# Main.net
KiCad netlist of a schematic drawn in Altium Designer
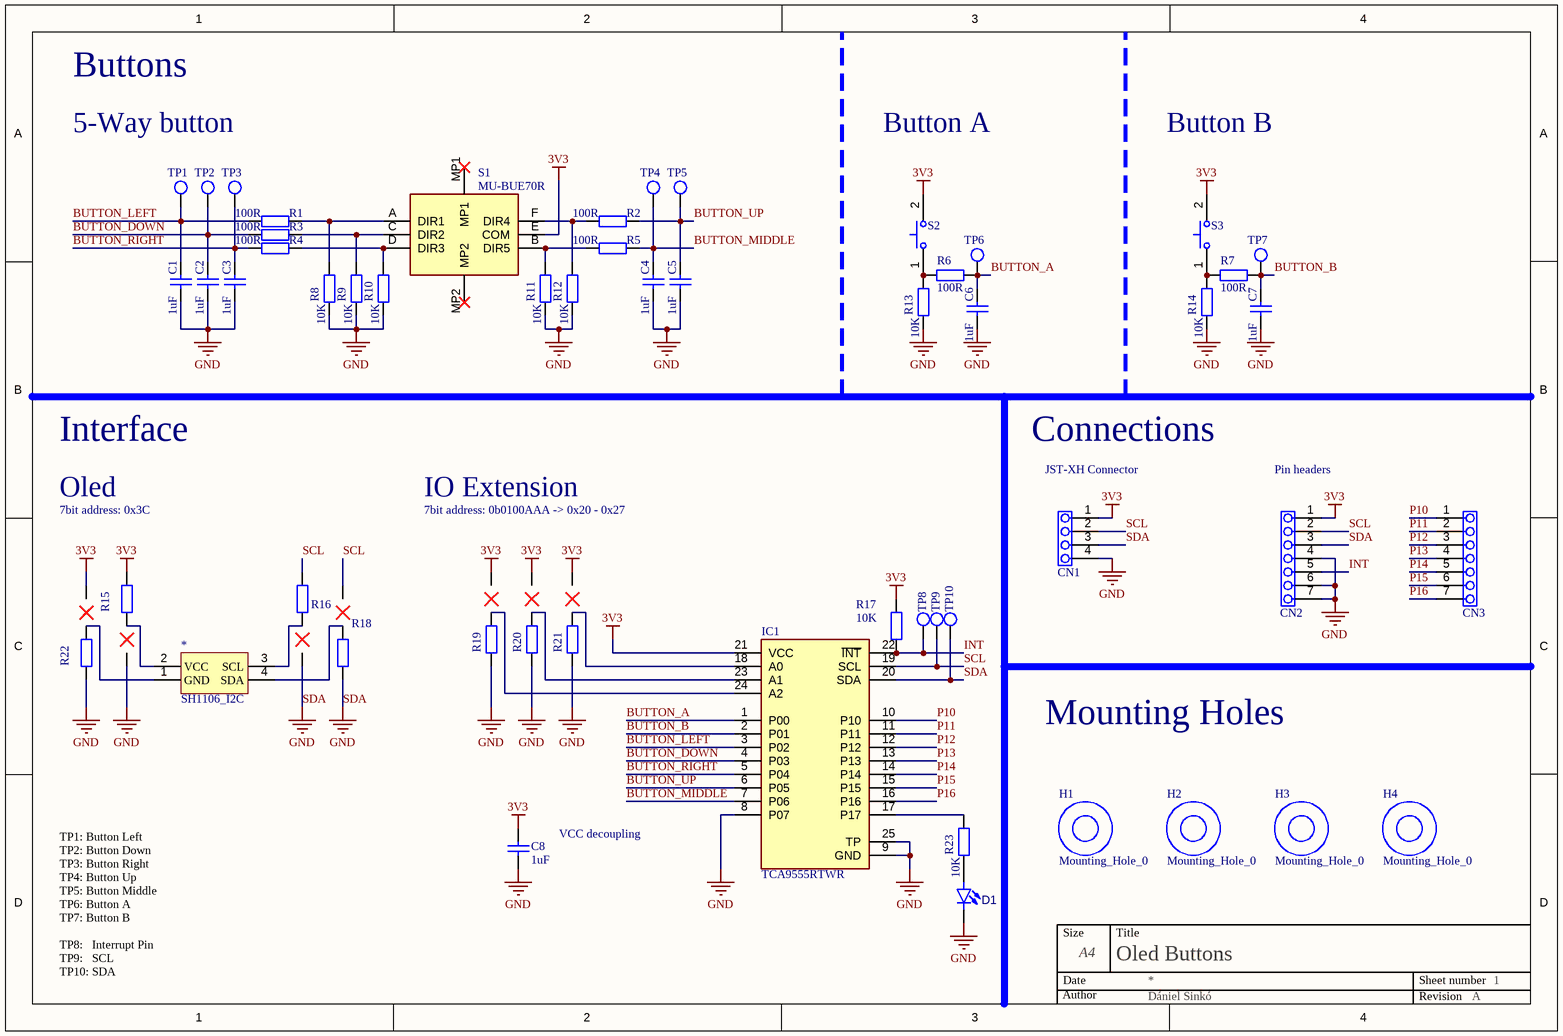
[diagram p0: Main.SchDoc]

(export (version "E")
  (design (tool "Eeschema 10.0.6"))
  (components
    (comp (ref "*")
      (value "SH1106_I2C")
      (footprint "SH1106_I2C")
      (libsource (lib "Generic_Schematic_Symbols") (part "SH1106_I2C"))
    )
    (comp (ref "C1")
      (value "1uF")
      (footprint "CAP0603")
      (description "Capacitor")
      (libsource (lib "Generic_Schematic_Symbols") (part "Capacitor"))
    )
    (comp (ref "C2")
      (value "1uF")
      (footprint "CAP0603")
      (description "Capacitor")
      (libsource (lib "Generic_Schematic_Symbols") (part "Capacitor"))
    )
    (comp (ref "C3")
      (value "1uF")
      (footprint "CAP0603")
      (description "Capacitor")
      (libsource (lib "Generic_Schematic_Symbols") (part "Capacitor"))
    )
    (comp (ref "C4")
      (value "1uF")
      (footprint "CAP0603")
      (description "Capacitor")
      (libsource (lib "Generic_Schematic_Symbols") (part "Capacitor"))
    )
    (comp (ref "C5")
      (value "1uF")
      (footprint "CAP0603")
      (description "Capacitor")
      (libsource (lib "Generic_Schematic_Symbols") (part "Capacitor"))
    )
    (comp (ref "C6")
      (value "1uF")
      (footprint "CAP0603")
      (description "Capacitor")
      (libsource (lib "Generic_Schematic_Symbols") (part "Capacitor"))
    )
    (comp (ref "C7")
      (value "1uF")
      (footprint "CAP0603")
      (description "Capacitor")
      (libsource (lib "Generic_Schematic_Symbols") (part "Capacitor"))
    )
    (comp (ref "C8")
      (value "1uF")
      (footprint "CAP0603")
      (description "Capacitor")
      (libsource (lib "Generic_Schematic_Symbols") (part "Capacitor"))
    )
    (comp (ref "CN1")
      (value "Pins 1x3")
      (footprint "PIN-1X4")
      (description "2.54mm")
      (libsource (lib "Generic_Schematic_Symbols") (part "Pin-1x4"))
    )
    (comp (ref "CN2")
      (value "Pins 1x3")
      (footprint "PIN-1X7")
      (description "2.54mm")
      (libsource (lib "Generic_Schematic_Symbols") (part "Pin-1x7"))
    )
    (comp (ref "CN3")
      (value "Pins 1x3")
      (footprint "PIN-1X7")
      (description "2.54mm")
      (libsource (lib "Generic_Schematic_Symbols") (part "Pin-1x7"))
    )
    (comp (ref "D1")
      (value "~")
      (footprint "LED0603")
      (description "Light Emitting Diode")
      (libsource (lib "Generic_Schematic_Symbols") (part "LED"))
    )
    (comp (ref "H1")
      (value "Mounting_Hole_0")
      (footprint "MOUNTING_HOLE_M3_0")
      (description "Mounting hole with no connectivity.")
      (libsource (lib "Generic_Schematic_Symbols") (part "Mounting_Hole_0"))
    )
    (comp (ref "H2")
      (value "Mounting_Hole_0")
      (footprint "MOUNTING_HOLE_M3_0")
      (description "Mounting hole with no connectivity.")
      (libsource (lib "Generic_Schematic_Symbols") (part "Mounting_Hole_0"))
    )
    (comp (ref "H3")
      (value "Mounting_Hole_0")
      (footprint "MOUNTING_HOLE_M3_0")
      (description "Mounting hole with no connectivity.")
      (libsource (lib "Generic_Schematic_Symbols") (part "Mounting_Hole_0"))
    )
    (comp (ref "H4")
      (value "Mounting_Hole_0")
      (footprint "MOUNTING_HOLE_M3_0")
      (description "Mounting hole with no connectivity.")
      (libsource (lib "Generic_Schematic_Symbols") (part "Mounting_Hole_0"))
    )
    (comp (ref "IC1")
      (value "TCA9555RTWR")
      (footprint "WQFN-24")
      (description "Integrated Circuit")
      (fields
        (field (name "MOUSER PART NUMBER") "595-TCA9555RTWR")
        (field (name "LCSC PART NUMBER") "C42420609")
      )
      (libsource (lib "Generic_Schematic_Symbols") (part "TCA9555RTWR"))
    )
    (comp (ref "R1")
      (value "100R")
      (footprint "RES0603")
      (description "Resistor")
      (libsource (lib "") (part "Resistor_1"))
    )
    (comp (ref "R2")
      (value "100R")
      (footprint "RES0603")
      (description "Resistor")
      (libsource (lib "") (part "Resistor_1"))
    )
    (comp (ref "R3")
      (value "100R")
      (footprint "RES0603")
      (description "Resistor")
      (libsource (lib "") (part "Resistor_1"))
    )
    (comp (ref "R4")
      (value "100R")
      (footprint "RES0603")
      (description "Resistor")
      (libsource (lib "") (part "Resistor_1"))
    )
    (comp (ref "R5")
      (value "100R")
      (footprint "RES0603")
      (description "Resistor")
      (libsource (lib "") (part "Resistor_1"))
    )
    (comp (ref "R6")
      (value "100R")
      (footprint "RES0603")
      (description "Resistor")
      (libsource (lib "") (part "Resistor_1"))
    )
    (comp (ref "R7")
      (value "100R")
      (footprint "RES0603")
      (description "Resistor")
      (libsource (lib "") (part "Resistor_1"))
    )
    (comp (ref "R8")
      (value "10K")
      (footprint "RES0603")
      (description "Resistor")
      (libsource (lib "Generic_Schematic_Symbols") (part "Resistor"))
    )
    (comp (ref "R9")
      (value "10K")
      (footprint "RES0603")
      (description "Resistor")
      (libsource (lib "Generic_Schematic_Symbols") (part "Resistor"))
    )
    (comp (ref "R10")
      (value "10K")
      (footprint "RES0603")
      (description "Resistor")
      (libsource (lib "Generic_Schematic_Symbols") (part "Resistor"))
    )
    (comp (ref "R11")
      (value "10K")
      (footprint "RES0603")
      (description "Resistor")
      (libsource (lib "Generic_Schematic_Symbols") (part "Resistor"))
    )
    (comp (ref "R12")
      (value "10K")
      (footprint "RES0603")
      (description "Resistor")
      (libsource (lib "Generic_Schematic_Symbols") (part "Resistor"))
    )
    (comp (ref "R13")
      (value "10K")
      (footprint "RES0603")
      (description "Resistor")
      (libsource (lib "Generic_Schematic_Symbols") (part "Resistor"))
    )
    (comp (ref "R14")
      (value "10K")
      (footprint "RES0603")
      (description "Resistor")
      (libsource (lib "Generic_Schematic_Symbols") (part "Resistor"))
    )
    (comp (ref "R15")
      (value "*")
      (footprint "RES0603 _SELECTION")
      (description "Resistor")
      (libsource (lib "") (part "Resistor_Selection_1"))
    )
    (comp (ref "R16")
      (value "*")
      (footprint "RES0603 _SELECTION")
      (description "Resistor")
      (libsource (lib "") (part "Resistor_Selection_2"))
    )
    (comp (ref "R17")
      (value "10K")
      (footprint "RES0603")
      (description "Resistor")
      (libsource (lib "Generic_Schematic_Symbols") (part "Resistor"))
    )
    (comp (ref "R18")
      (value "*")
      (footprint "RES0603 _SELECTION")
      (description "Resistor")
      (libsource (lib "Generic_Schematic_Symbols") (part "Resistor_Selection"))
    )
    (comp (ref "R19")
      (value "*")
      (footprint "RES0603 _SELECTION")
      (description "Resistor")
      (libsource (lib "Generic_Schematic_Symbols") (part "Resistor_Selection"))
    )
    (comp (ref "R20")
      (value "*")
      (footprint "RES0603 _SELECTION")
      (description "Resistor")
      (libsource (lib "Generic_Schematic_Symbols") (part "Resistor_Selection"))
    )
    (comp (ref "R21")
      (value "*")
      (footprint "RES0603 _SELECTION")
      (description "Resistor")
      (libsource (lib "Generic_Schematic_Symbols") (part "Resistor_Selection"))
    )
    (comp (ref "R22")
      (value "*")
      (footprint "RES0603 _SELECTION")
      (description "Resistor")
      (libsource (lib "") (part "Resistor_Selection_3"))
    )
    (comp (ref "R23")
      (value "10K")
      (footprint "RES0603")
      (description "Resistor")
      (libsource (lib "Generic_Schematic_Symbols") (part "Resistor"))
    )
    (comp (ref "S1")
      (value "MU-BUE70R")
      (footprint "MUBUE70R")
      (description "Switch")
      (fields (field (name "LCSC PART NUMBER") "C2858287"))
      (libsource (lib "Buttons") (part "MU-BUE70R"))
    )
    (comp (ref "S2")
      (value "SKPMANE010")
      (footprint "SKPMAPE010")
      (description "Switch (2-Pin Push)")
      (fields (field (name "MOUSER PART NUMBER") "688-SKPMAN"))
      (libsource (lib "Buttons") (part "SKPMANE010"))
    )
    (comp (ref "S3")
      (value "SKPMANE010")
      (footprint "SKPMAPE010")
      (description "Switch (2-Pin Push)")
      (fields (field (name "MOUSER PART NUMBER") "688-SKPMAN"))
      (libsource (lib "Buttons") (part "SKPMANE010"))
    )
    (comp (ref "TP1")
      (value "Test Point")
      (footprint "TP_PAD")
      (libsource (lib "Generic_Schematic_Symbols") (part "Test Point"))
    )
    (comp (ref "TP2")
      (value "Test Point")
      (footprint "TP_PAD")
      (libsource (lib "Generic_Schematic_Symbols") (part "Test Point"))
    )
    (comp (ref "TP3")
      (value "Test Point")
      (footprint "TP_PAD")
      (libsource (lib "Generic_Schematic_Symbols") (part "Test Point"))
    )
    (comp (ref "TP4")
      (value "Test Point")
      (footprint "TP_PAD")
      (libsource (lib "Generic_Schematic_Symbols") (part "Test Point"))
    )
    (comp (ref "TP5")
      (value "Test Point")
      (footprint "TP_PAD")
      (libsource (lib "Generic_Schematic_Symbols") (part "Test Point"))
    )
    (comp (ref "TP6")
      (value "Test Point")
      (footprint "TP_PAD")
      (libsource (lib "Generic_Schematic_Symbols") (part "Test Point"))
    )
    (comp (ref "TP7")
      (value "Test Point")
      (footprint "TP_PAD")
      (libsource (lib "Generic_Schematic_Symbols") (part "Test Point"))
    )
    (comp (ref "TP8")
      (value "Test Point")
      (footprint "TP_PAD")
      (libsource (lib "Generic_Schematic_Symbols") (part "Test Point"))
    )
    (comp (ref "TP9")
      (value "Test Point")
      (footprint "TP_PAD")
      (libsource (lib "Generic_Schematic_Symbols") (part "Test Point"))
    )
    (comp (ref "TP10")
      (value "Test Point")
      (footprint "TP_PAD")
      (libsource (lib "Generic_Schematic_Symbols") (part "Test Point"))
    )
  )
  (nets
    (net (code "1") (name "/BUTTON_A") (class "Default")
      (node (ref "C6") (pin "2") (pinfunction "2_2") (pintype "passive"))
      (node (ref "IC1") (pin "1") (pinfunction "P00_1") (pintype "passive"))
      (node (ref "R6") (pin "1") (pinfunction "1_1") (pintype "passive"))
      (node (ref "TP6") (pin "1") (pintype "passive"))
    )
    (net (code "2") (name "/BUTTON_B") (class "Default")
      (node (ref "C7") (pin "2") (pinfunction "2_2") (pintype "passive"))
      (node (ref "IC1") (pin "2") (pinfunction "P01_2") (pintype "passive"))
      (node (ref "R7") (pin "1") (pinfunction "1_1") (pintype "passive"))
      (node (ref "TP7") (pin "1") (pintype "passive"))
    )
    (net (code "3") (name "/BUTTON_DOWN") (class "Default")
      (node (ref "C2") (pin "2") (pinfunction "2_2") (pintype "passive"))
      (node (ref "IC1") (pin "4") (pinfunction "P03_4") (pintype "passive"))
      (node (ref "R3") (pin "2") (pinfunction "2_2") (pintype "passive"))
      (node (ref "TP2") (pin "1") (pintype "passive"))
    )
    (net (code "4") (name "/BUTTON_LEFT") (class "Default")
      (node (ref "C1") (pin "2") (pinfunction "2_2") (pintype "passive"))
      (node (ref "IC1") (pin "3") (pinfunction "P02_3") (pintype "passive"))
      (node (ref "R1") (pin "2") (pinfunction "2_2") (pintype "passive"))
      (node (ref "TP1") (pin "1") (pintype "passive"))
    )
    (net (code "5") (name "/BUTTON_MIDDLE") (class "Default")
      (node (ref "C4") (pin "2") (pinfunction "2_2") (pintype "passive"))
      (node (ref "IC1") (pin "7") (pinfunction "P06_7") (pintype "passive"))
      (node (ref "R5") (pin "1") (pinfunction "1_1") (pintype "passive"))
      (node (ref "TP4") (pin "1") (pintype "passive"))
    )
    (net (code "6") (name "/BUTTON_RIGHT") (class "Default")
      (node (ref "C3") (pin "2") (pinfunction "2_2") (pintype "passive"))
      (node (ref "IC1") (pin "5") (pinfunction "P04_5") (pintype "passive"))
      (node (ref "R4") (pin "2") (pinfunction "2_2") (pintype "passive"))
      (node (ref "TP3") (pin "1") (pintype "passive"))
    )
    (net (code "7") (name "/BUTTON_UP") (class "Default")
      (node (ref "C5") (pin "2") (pinfunction "2_2") (pintype "passive"))
      (node (ref "IC1") (pin "6") (pinfunction "P05_6") (pintype "passive"))
      (node (ref "R2") (pin "1") (pinfunction "1_1") (pintype "passive"))
      (node (ref "TP5") (pin "1") (pintype "passive"))
    )
    (net (code "8") (name "/INT") (class "Default")
      (node (ref "CN2") (pin "5") (pinfunction "5_5") (pintype "passive"))
      (node (ref "IC1") (pin "22") (pinfunction "~{INT}_22") (pintype "passive"))
      (node (ref "R17") (pin "1") (pinfunction "1_1") (pintype "passive"))
      (node (ref "TP8") (pin "1") (pintype "passive"))
    )
    (net (code "9") (name "/P10") (class "Default")
      (node (ref "CN3") (pin "1") (pinfunction "1_1") (pintype "passive"))
      (node (ref "IC1") (pin "10") (pinfunction "P10_10") (pintype "passive"))
    )
    (net (code "10") (name "/P11") (class "Default")
      (node (ref "CN3") (pin "2") (pinfunction "2_2") (pintype "passive"))
      (node (ref "IC1") (pin "11") (pinfunction "P11_11") (pintype "passive"))
    )
    (net (code "11") (name "/P12") (class "Default")
      (node (ref "CN3") (pin "3") (pinfunction "3_3") (pintype "passive"))
      (node (ref "IC1") (pin "12") (pinfunction "P12_12") (pintype "passive"))
    )
    (net (code "12") (name "/P13") (class "Default")
      (node (ref "CN3") (pin "4") (pinfunction "4_4") (pintype "passive"))
      (node (ref "IC1") (pin "13") (pinfunction "P13_13") (pintype "passive"))
    )
    (net (code "13") (name "/P14") (class "Default")
      (node (ref "CN3") (pin "5") (pinfunction "5_5") (pintype "passive"))
      (node (ref "IC1") (pin "14") (pinfunction "P14_14") (pintype "passive"))
    )
    (net (code "14") (name "/P15") (class "Default")
      (node (ref "CN3") (pin "6") (pinfunction "6_6") (pintype "passive"))
      (node (ref "IC1") (pin "15") (pinfunction "P15_15") (pintype "passive"))
    )
    (net (code "15") (name "/P16") (class "Default")
      (node (ref "CN3") (pin "7") (pinfunction "7_7") (pintype "passive"))
      (node (ref "IC1") (pin "16") (pinfunction "P16_16") (pintype "passive"))
    )
    (net (code "16") (name "/SCL") (class "Default")
      (node (ref "CN1") (pin "2") (pinfunction "2_2") (pintype "passive"))
      (node (ref "CN2") (pin "2") (pinfunction "2_2") (pintype "passive"))
      (node (ref "IC1") (pin "19") (pinfunction "SCL_19") (pintype "passive"))
      (node (ref "R16") (pin "1") (pinfunction "1_1") (pintype "passive"))
      (node (ref "R18") (pin "3") (pinfunction "3_3") (pintype "passive"))
      (node (ref "TP9") (pin "1") (pintype "passive"))
    )
    (net (code "17") (name "3V3") (class "Default")
      (node (ref "C8") (pin "2") (pinfunction "2_2") (pintype "passive"))
      (node (ref "CN1") (pin "1") (pinfunction "1_1") (pintype "passive"))
      (node (ref "CN2") (pin "1") (pinfunction "1_1") (pintype "passive"))
      (node (ref "IC1") (pin "21") (pinfunction "VCC_21") (pintype "passive"))
      (node (ref "R15") (pin "1") (pinfunction "1_1") (pintype "passive"))
      (node (ref "R17") (pin "2") (pinfunction "2_2") (pintype "passive"))
      (node (ref "R19") (pin "3") (pinfunction "3_3") (pintype "passive"))
      (node (ref "R20") (pin "3") (pinfunction "3_3") (pintype "passive"))
      (node (ref "R21") (pin "3") (pinfunction "3_3") (pintype "passive"))
      (node (ref "R22") (pin "3") (pinfunction "3_3") (pintype "passive"))
      (node (ref "S1") (pin "E") (pinfunction "COM_E") (pintype "passive"))
      (node (ref "S2") (pin "2") (pinfunction "2_2") (pintype "passive"))
      (node (ref "S3") (pin "2") (pinfunction "2_2") (pintype "passive"))
    )
    (net (code "18") (name "GND") (class "Default")
      (node (ref "C1") (pin "1") (pinfunction "1_1") (pintype "passive"))
      (node (ref "C2") (pin "1") (pinfunction "1_1") (pintype "passive"))
      (node (ref "C3") (pin "1") (pinfunction "1_1") (pintype "passive"))
      (node (ref "C4") (pin "1") (pinfunction "1_1") (pintype "passive"))
      (node (ref "C5") (pin "1") (pinfunction "1_1") (pintype "passive"))
      (node (ref "C6") (pin "1") (pinfunction "1_1") (pintype "passive"))
      (node (ref "C7") (pin "1") (pinfunction "1_1") (pintype "passive"))
      (node (ref "C8") (pin "1") (pinfunction "1_1") (pintype "passive"))
      (node (ref "CN1") (pin "3") (pinfunction "3_3") (pintype "passive"))
      (node (ref "CN1") (pin "4") (pinfunction "4_4") (pintype "passive"))
      (node (ref "CN2") (pin "3") (pinfunction "3_3") (pintype "passive"))
      (node (ref "CN2") (pin "4") (pinfunction "4_4") (pintype "passive"))
      (node (ref "CN2") (pin "6") (pinfunction "6_6") (pintype "passive"))
      (node (ref "CN2") (pin "7") (pinfunction "7_7") (pintype "passive"))
      (node (ref "D1") (pin "1") (pinfunction "K_1") (pintype "passive"))
      (node (ref "IC1") (pin "20") (pinfunction "SDA_20") (pintype "passive"))
      (node (ref "IC1") (pin "25") (pinfunction "TP_25") (pintype "passive"))
      (node (ref "IC1") (pin "8") (pinfunction "P07_8") (pintype "passive"))
      (node (ref "IC1") (pin "9") (pinfunction "GND_9") (pintype "passive"))
      (node (ref "R10") (pin "1") (pinfunction "1_1") (pintype "passive"))
      (node (ref "R11") (pin "1") (pinfunction "1_1") (pintype "passive"))
      (node (ref "R12") (pin "1") (pinfunction "1_1") (pintype "passive"))
      (node (ref "R13") (pin "1") (pinfunction "1_1") (pintype "passive"))
      (node (ref "R14") (pin "1") (pinfunction "1_1") (pintype "passive"))
      (node (ref "R15") (pin "3") (pinfunction "3_3") (pintype "passive"))
      (node (ref "R16") (pin "3") (pinfunction "3_3") (pintype "passive"))
      (node (ref "R18") (pin "1") (pinfunction "1_1") (pintype "passive"))
      (node (ref "R19") (pin "1") (pinfunction "1_1") (pintype "passive"))
      (node (ref "R20") (pin "1") (pinfunction "1_1") (pintype "passive"))
      (node (ref "R21") (pin "1") (pinfunction "1_1") (pintype "passive"))
      (node (ref "R22") (pin "1") (pinfunction "1_1") (pintype "passive"))
      (node (ref "R8") (pin "1") (pinfunction "1_1") (pintype "passive"))
      (node (ref "R9") (pin "1") (pinfunction "1_1") (pintype "passive"))
      (node (ref "TP10") (pin "1") (pintype "passive"))
    )
    (net (code "19") (name "Net-(*-GND)") (class "Default")
      (node (ref "*") (pin "1") (pinfunction "GND_1") (pintype "passive"))
      (node (ref "R22") (pin "2") (pinfunction "2_2") (pintype "passive"))
    )
    (net (code "20") (name "Net-(*-SCL)") (class "Default")
      (node (ref "*") (pin "3") (pinfunction "SCL_3") (pintype "passive"))
      (node (ref "R16") (pin "2") (pinfunction "2_2") (pintype "passive"))
    )
    (net (code "21") (name "Net-(*-SDA)") (class "Default")
      (node (ref "*") (pin "4") (pinfunction "SDA_4") (pintype "passive"))
      (node (ref "R18") (pin "2") (pinfunction "2_2") (pintype "passive"))
    )
    (net (code "22") (name "Net-(*-VCC)") (class "Default")
      (node (ref "*") (pin "2") (pinfunction "VCC_2") (pintype "passive"))
      (node (ref "R15") (pin "2") (pinfunction "2_2") (pintype "passive"))
    )
    (net (code "23") (name "Net-(D1-A)") (class "Default")
      (node (ref "D1") (pin "2") (pinfunction "A_2") (pintype "passive"))
      (node (ref "R23") (pin "1") (pinfunction "1_1") (pintype "passive"))
    )
    (net (code "24") (name "Net-(IC1-A0)") (class "Default")
      (node (ref "IC1") (pin "18") (pinfunction "A0_18") (pintype "passive"))
      (node (ref "R21") (pin "2") (pinfunction "2_2") (pintype "passive"))
    )
    (net (code "25") (name "Net-(IC1-A1)") (class "Default")
      (node (ref "IC1") (pin "23") (pinfunction "A1_23") (pintype "passive"))
      (node (ref "R20") (pin "2") (pinfunction "2_2") (pintype "passive"))
    )
    (net (code "26") (name "Net-(IC1-A2)") (class "Default")
      (node (ref "IC1") (pin "24") (pinfunction "A2_24") (pintype "passive"))
      (node (ref "R19") (pin "2") (pinfunction "2_2") (pintype "passive"))
    )
    (net (code "27") (name "Net-(IC1-P17)") (class "Default")
      (node (ref "IC1") (pin "17") (pinfunction "P17_17") (pintype "passive"))
      (node (ref "R23") (pin "2") (pinfunction "2_2") (pintype "passive"))
    )
    (net (code "28") (name "Net-(R13-Pad2)") (class "Default")
      (node (ref "R13") (pin "2") (pinfunction "2_2") (pintype "passive"))
      (node (ref "R6") (pin "2") (pinfunction "2_2") (pintype "passive"))
      (node (ref "S2") (pin "1") (pinfunction "1_1") (pintype "passive"))
    )
    (net (code "29") (name "Net-(R14-Pad2)") (class "Default")
      (node (ref "R14") (pin "2") (pinfunction "2_2") (pintype "passive"))
      (node (ref "R7") (pin "2") (pinfunction "2_2") (pintype "passive"))
      (node (ref "S3") (pin "1") (pinfunction "1_1") (pintype "passive"))
    )
    (net (code "30") (name "Net-(S1-DIR1)") (class "Default")
      (node (ref "R1") (pin "1") (pinfunction "1_1") (pintype "passive"))
      (node (ref "R8") (pin "2") (pinfunction "2_2") (pintype "passive"))
      (node (ref "S1") (pin "A") (pinfunction "DIR1_A") (pintype "passive"))
    )
    (net (code "31") (name "Net-(S1-DIR2)") (class "Default")
      (node (ref "R3") (pin "1") (pinfunction "1_1") (pintype "passive"))
      (node (ref "R9") (pin "2") (pinfunction "2_2") (pintype "passive"))
      (node (ref "S1") (pin "C") (pinfunction "DIR2_C") (pintype "passive"))
    )
    (net (code "32") (name "Net-(S1-DIR3)") (class "Default")
      (node (ref "R10") (pin "2") (pinfunction "2_2") (pintype "passive"))
      (node (ref "R4") (pin "1") (pinfunction "1_1") (pintype "passive"))
      (node (ref "S1") (pin "D") (pinfunction "DIR3_D") (pintype "passive"))
    )
    (net (code "33") (name "Net-(S1-DIR4)") (class "Default")
      (node (ref "R12") (pin "2") (pinfunction "2_2") (pintype "passive"))
      (node (ref "R2") (pin "2") (pinfunction "2_2") (pintype "passive"))
      (node (ref "S1") (pin "F") (pinfunction "DIR4_F") (pintype "passive"))
    )
    (net (code "34") (name "Net-(S1-DIR5)") (class "Default")
      (node (ref "R11") (pin "2") (pinfunction "2_2") (pintype "passive"))
      (node (ref "R5") (pin "2") (pinfunction "2_2") (pintype "passive"))
      (node (ref "S1") (pin "B") (pinfunction "DIR5_B") (pintype "passive"))
    )
    (net (code "35") (name "unconnected-(S1-PadMP1)") (class "Default")
      (node (ref "S1") (pin "MP1") (pinfunction "MP1_MP1") (pintype "passive+no_connect"))
    )
    (net (code "36") (name "unconnected-(S1-PadMP2)") (class "Default")
      (node (ref "S1") (pin "MP2") (pinfunction "MP2_MP2") (pintype "passive+no_connect"))
    )
  )
)
